# USB2_0_Connector.net
KiCad netlist of a schematic drawn in Altium Designer
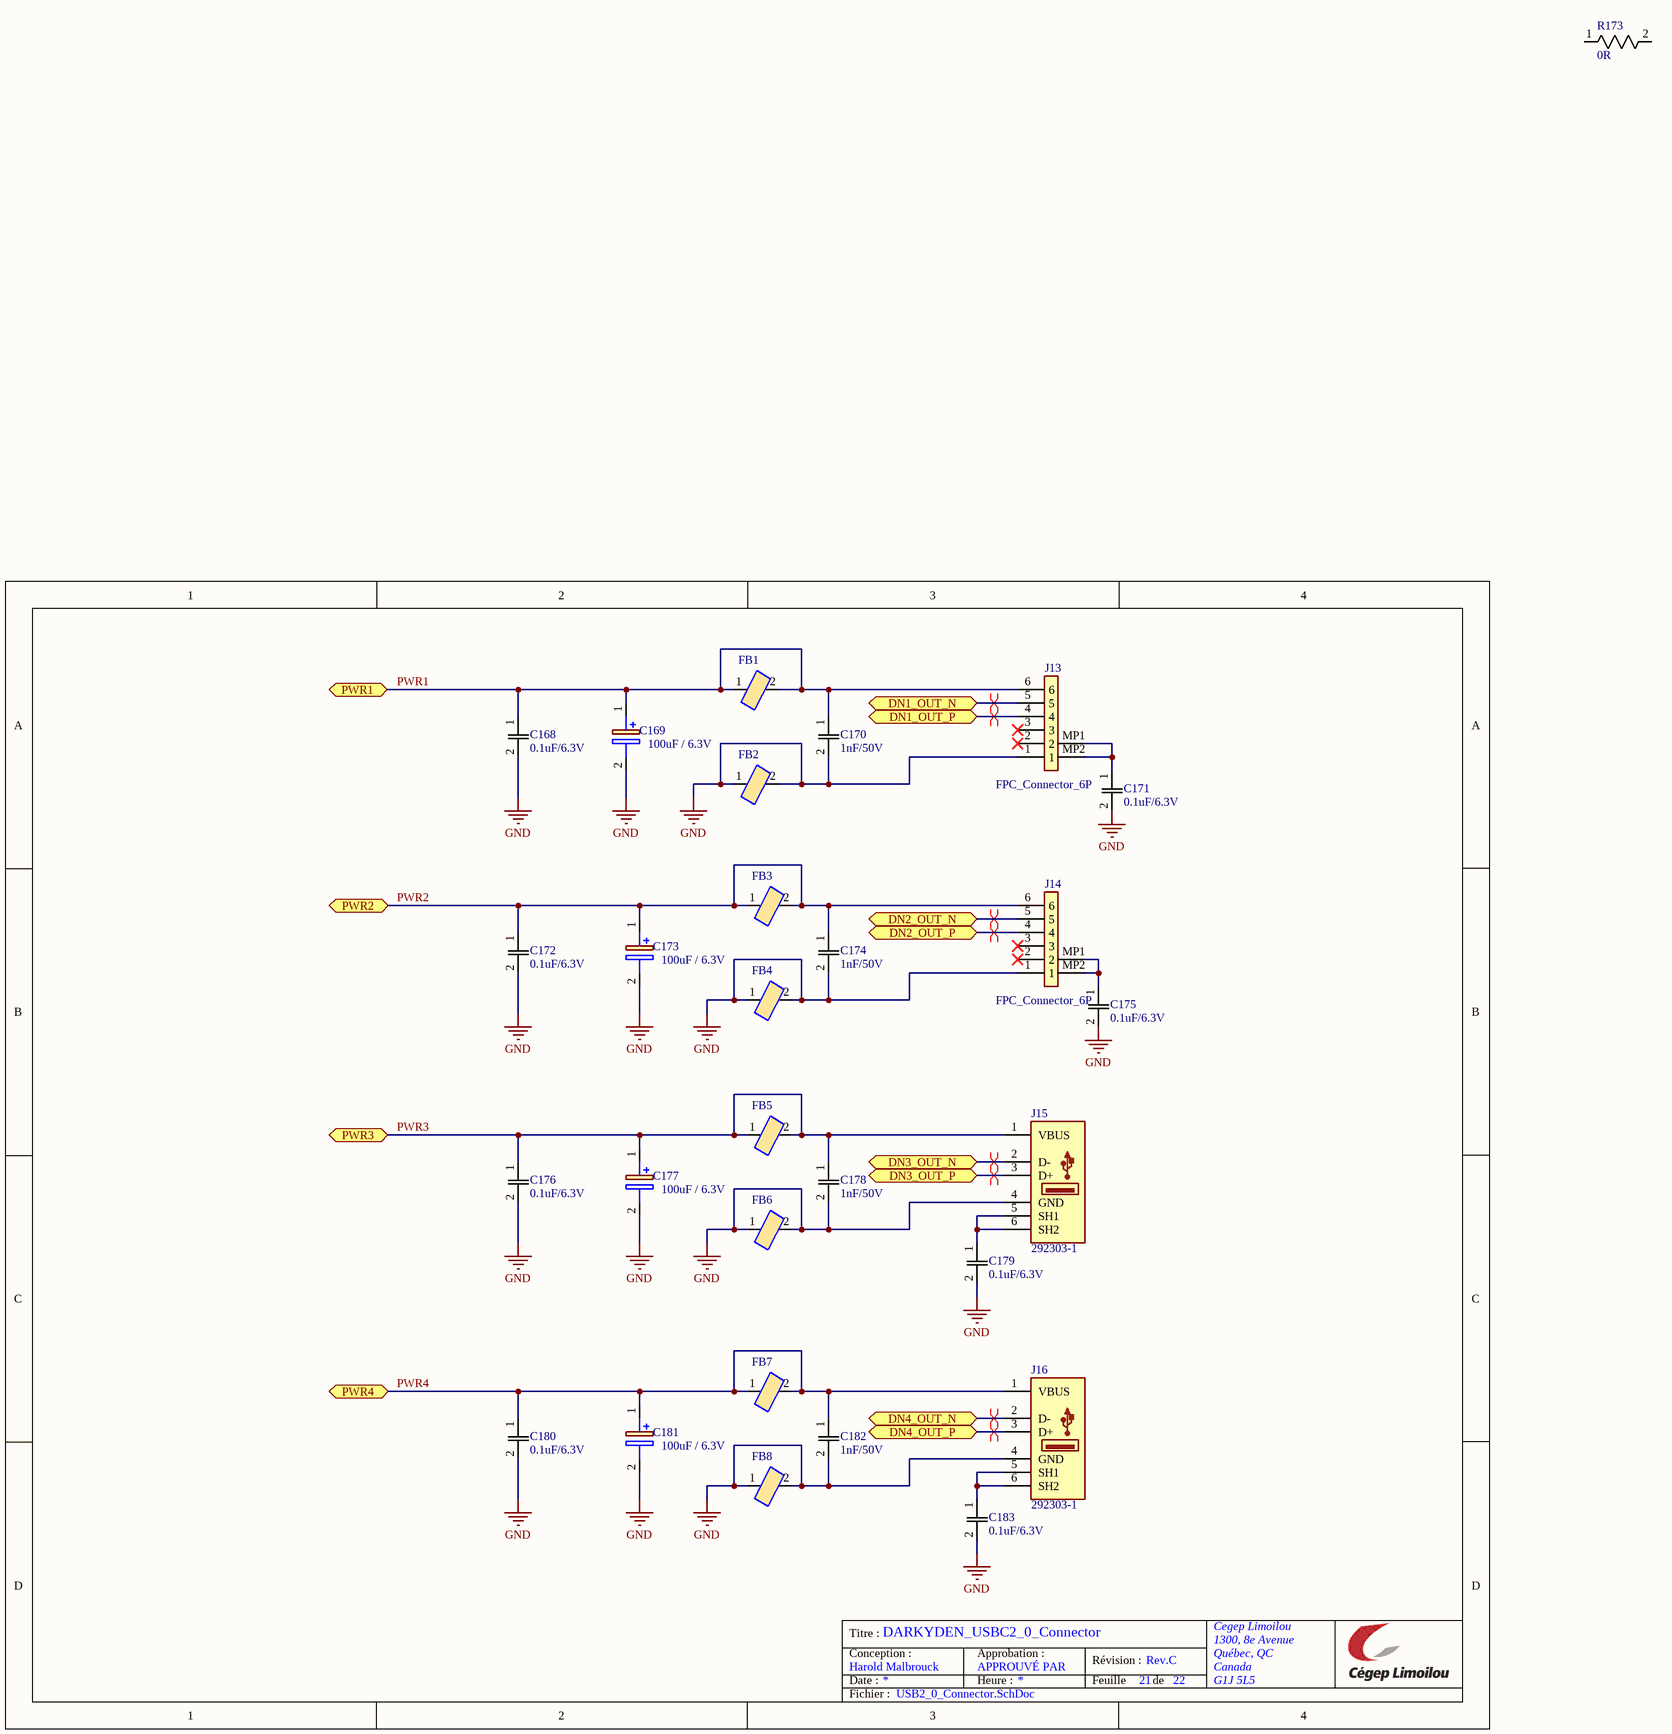
[diagram p0: USB2_0_Connector.SchDoc]

(export (version "E")
  (design (tool "Eeschema 10.0.6"))
  (components
    (comp (ref "C168")
      (value "0.1uF/6.3V")
      (footprint "SamacSys:C0805")
      (description "0.1uF 6.3V X7R 10% Pad SMD 0805 125C T/R")
      (fields
        (field (name "MANUFACTURER_PART_NUMBER") "C0805C104K9RACTU")
        (field (name "MOUSER PART NUMBER") "80-C0805C104K9R")
      )
      (libsource (lib "SamacSys") (part "C0805C104K9RACTU"))
    )
    (comp (ref "C169")
      (value "100uF / 6.3V")
      (footprint "SamacSys:EEE0GA101SR")
      (description "100uF 6.3V 20% Cap Aluminum Lytic  SMD 0.36 Ohm 240mA 2000h 105C Automotive T/R")
      (fields
        (field (name "MANUFACTURER_PART_NUMBER") "EEE-FPJ101UAR")
        (field (name "MOUSER PART NUMBER") "667-EEE-FPJ101UAR")
      )
      (libsource (lib "SamacSys") (part "EEE-FPJ101UAR"))
    )
    (comp (ref "C170")
      (value "1nF/50V")
      (footprint "SamacSys:CAPC2012X88N")
      (description "1000 pF ±10% 50V Ceramic Capacitor X7R 0805 (2012 Metric)")
      (fields (field (name "MANUFACTURER_PART_NUMBER") "C0805C102K5RAC-TU"))
      (libsource (lib "SamacSys") (part "C0805C102K5RAC-TU"))
    )
    (comp (ref "C171")
      (value "0.1uF/6.3V")
      (footprint "SamacSys:C0805")
      (description "0.1uF 6.3V X7R 10% Pad SMD 0805 125C T/R")
      (fields
        (field (name "MANUFACTURER_PART_NUMBER") "C0805C104K9RACTU")
        (field (name "MOUSER PART NUMBER") "80-C0805C104K9R")
      )
      (libsource (lib "SamacSys") (part "C0805C104K9RACTU"))
    )
    (comp (ref "C172")
      (value "0.1uF/6.3V")
      (footprint "SamacSys:C0805")
      (description "0.1uF 6.3V X7R 10% Pad SMD 0805 125C T/R")
      (fields
        (field (name "MANUFACTURER_PART_NUMBER") "C0805C104K9RACTU")
        (field (name "MOUSER PART NUMBER") "80-C0805C104K9R")
      )
      (libsource (lib "SamacSys") (part "C0805C104K9RACTU"))
    )
    (comp (ref "C173")
      (value "100uF / 6.3V")
      (footprint "SamacSys:EEE0GA101SR")
      (description "100uF 6.3V 20% Cap Aluminum Lytic  SMD 0.36 Ohm 240mA 2000h 105C Automotive T/R")
      (fields
        (field (name "MANUFACTURER_PART_NUMBER") "EEE-FPJ101UAR")
        (field (name "MOUSER PART NUMBER") "667-EEE-FPJ101UAR")
      )
      (libsource (lib "SamacSys") (part "EEE-FPJ101UAR"))
    )
    (comp (ref "C174")
      (value "1nF/50V")
      (footprint "SamacSys:CAPC2012X88N")
      (description "1000 pF ±10% 50V Ceramic Capacitor X7R 0805 (2012 Metric)")
      (fields (field (name "MANUFACTURER_PART_NUMBER") "C0805C102K5RAC-TU"))
      (libsource (lib "SamacSys") (part "C0805C102K5RAC-TU"))
    )
    (comp (ref "C175")
      (value "0.1uF/6.3V")
      (footprint "SamacSys:C0805")
      (description "0.1uF 6.3V X7R 10% Pad SMD 0805 125C T/R")
      (fields
        (field (name "MANUFACTURER_PART_NUMBER") "C0805C104K9RACTU")
        (field (name "MOUSER PART NUMBER") "80-C0805C104K9R")
      )
      (libsource (lib "SamacSys") (part "C0805C104K9RACTU"))
    )
    (comp (ref "C176")
      (value "0.1uF/6.3V")
      (footprint "SamacSys:C0805")
      (description "0.1uF 6.3V X7R 10% Pad SMD 0805 125C T/R")
      (fields
        (field (name "MANUFACTURER_PART_NUMBER") "C0805C104K9RACTU")
        (field (name "MOUSER PART NUMBER") "80-C0805C104K9R")
      )
      (libsource (lib "SamacSys") (part "C0805C104K9RACTU"))
    )
    (comp (ref "C177")
      (value "100uF / 6.3V")
      (footprint "SamacSys:EEE0GA101SR")
      (description "100uF 6.3V 20% Cap Aluminum Lytic  SMD 0.36 Ohm 240mA 2000h 105C Automotive T/R")
      (fields
        (field (name "MANUFACTURER_PART_NUMBER") "EEE-FPJ101UAR")
        (field (name "MOUSER PART NUMBER") "667-EEE-FPJ101UAR")
      )
      (libsource (lib "SamacSys") (part "EEE-FPJ101UAR"))
    )
    (comp (ref "C178")
      (value "1nF/50V")
      (footprint "SamacSys:CAPC2012X88N")
      (description "1000 pF ±10% 50V Ceramic Capacitor X7R 0805 (2012 Metric)")
      (fields (field (name "MANUFACTURER_PART_NUMBER") "C0805C102K5RAC-TU"))
      (libsource (lib "SamacSys") (part "C0805C102K5RAC-TU"))
    )
    (comp (ref "C179")
      (value "0.1uF/6.3V")
      (footprint "SamacSys:C0805")
      (description "0.1uF 6.3V X7R 10% Pad SMD 0805 125C T/R")
      (fields
        (field (name "MANUFACTURER_PART_NUMBER") "C0805C104K9RACTU")
        (field (name "MOUSER PART NUMBER") "80-C0805C104K9R")
      )
      (libsource (lib "SamacSys") (part "C0805C104K9RACTU"))
    )
    (comp (ref "C180")
      (value "0.1uF/6.3V")
      (footprint "SamacSys:C0805")
      (description "0.1uF 6.3V X7R 10% Pad SMD 0805 125C T/R")
      (fields
        (field (name "MANUFACTURER_PART_NUMBER") "C0805C104K9RACTU")
        (field (name "MOUSER PART NUMBER") "80-C0805C104K9R")
      )
      (libsource (lib "SamacSys") (part "C0805C104K9RACTU"))
    )
    (comp (ref "C181")
      (value "100uF / 6.3V")
      (footprint "SamacSys:EEE0GA101SR")
      (description "100uF 6.3V 20% Cap Aluminum Lytic  SMD 0.36 Ohm 240mA 2000h 105C Automotive T/R")
      (fields
        (field (name "MANUFACTURER_PART_NUMBER") "EEE-FPJ101UAR")
        (field (name "MOUSER PART NUMBER") "667-EEE-FPJ101UAR")
      )
      (libsource (lib "SamacSys") (part "EEE-FPJ101UAR"))
    )
    (comp (ref "C182")
      (value "1nF/50V")
      (footprint "SamacSys:CAPC2012X88N")
      (description "1000 pF ±10% 50V Ceramic Capacitor X7R 0805 (2012 Metric)")
      (fields (field (name "MANUFACTURER_PART_NUMBER") "C0805C102K5RAC-TU"))
      (libsource (lib "SamacSys") (part "C0805C102K5RAC-TU"))
    )
    (comp (ref "C183")
      (value "0.1uF/6.3V")
      (footprint "SamacSys:C0805")
      (description "0.1uF 6.3V X7R 10% Pad SMD 0805 125C T/R")
      (fields
        (field (name "MANUFACTURER_PART_NUMBER") "C0805C104K9RACTU")
        (field (name "MOUSER PART NUMBER") "80-C0805C104K9R")
      )
      (libsource (lib "SamacSys") (part "C0805C104K9RACTU"))
    )
    (comp (ref "FB1")
      (value "220R / 100MHz")
      (footprint "SamacSys:BLM18SP221SN1B")
      (description "Ferrite Beads Multi-Layer 220Ohm 25% 100MHz 2A 50mOhm DCR 0603 Paper T/R")
      (fields
        (field (name "MANUFACTURER_PART_NUMBER") "BLM18EG221SN1D")
        (field (name "MOUSER PART NUMBER") "81-BLM18EG221SN1D")
      )
      (libsource (lib "SamacSys") (part "BLM18EG221SN1D"))
    )
    (comp (ref "FB2")
      (value "220R / 100MHz")
      (footprint "SamacSys:BLM18SP221SN1B")
      (description "Ferrite Beads Multi-Layer 220Ohm 25% 100MHz 2A 50mOhm DCR 0603 Paper T/R")
      (fields
        (field (name "MANUFACTURER_PART_NUMBER") "BLM18EG221SN1D")
        (field (name "MOUSER PART NUMBER") "81-BLM18EG221SN1D")
      )
      (libsource (lib "SamacSys") (part "BLM18EG221SN1D"))
    )
    (comp (ref "FB3")
      (value "220R / 100MHz")
      (footprint "SamacSys:BLM18SP221SN1B")
      (description "Ferrite Beads Multi-Layer 220Ohm 25% 100MHz 2A 50mOhm DCR 0603 Paper T/R")
      (fields
        (field (name "MANUFACTURER_PART_NUMBER") "BLM18EG221SN1D")
        (field (name "MOUSER PART NUMBER") "81-BLM18EG221SN1D")
      )
      (libsource (lib "SamacSys") (part "BLM18EG221SN1D"))
    )
    (comp (ref "FB4")
      (value "220R / 100MHz")
      (footprint "SamacSys:BLM18SP221SN1B")
      (description "Ferrite Beads Multi-Layer 220Ohm 25% 100MHz 2A 50mOhm DCR 0603 Paper T/R")
      (fields
        (field (name "MANUFACTURER_PART_NUMBER") "BLM18EG221SN1D")
        (field (name "MOUSER PART NUMBER") "81-BLM18EG221SN1D")
      )
      (libsource (lib "SamacSys") (part "BLM18EG221SN1D"))
    )
    (comp (ref "FB5")
      (value "220R / 100MHz")
      (footprint "SamacSys:BLM18SP221SN1B")
      (description "Ferrite Beads Multi-Layer 220Ohm 25% 100MHz 2A 50mOhm DCR 0603 Paper T/R")
      (fields
        (field (name "MANUFACTURER_PART_NUMBER") "BLM18EG221SN1D")
        (field (name "MOUSER PART NUMBER") "81-BLM18EG221SN1D")
      )
      (libsource (lib "SamacSys") (part "BLM18EG221SN1D"))
    )
    (comp (ref "FB6")
      (value "220R / 100MHz")
      (footprint "SamacSys:BLM18SP221SN1B")
      (description "Ferrite Beads Multi-Layer 220Ohm 25% 100MHz 2A 50mOhm DCR 0603 Paper T/R")
      (fields
        (field (name "MANUFACTURER_PART_NUMBER") "BLM18EG221SN1D")
        (field (name "MOUSER PART NUMBER") "81-BLM18EG221SN1D")
      )
      (libsource (lib "SamacSys") (part "BLM18EG221SN1D"))
    )
    (comp (ref "FB7")
      (value "220R / 100MHz")
      (footprint "SamacSys:BLM18SP221SN1B")
      (description "Ferrite Beads Multi-Layer 220Ohm 25% 100MHz 2A 50mOhm DCR 0603 Paper T/R")
      (fields
        (field (name "MANUFACTURER_PART_NUMBER") "BLM18EG221SN1D")
        (field (name "MOUSER PART NUMBER") "81-BLM18EG221SN1D")
      )
      (libsource (lib "SamacSys") (part "BLM18EG221SN1D"))
    )
    (comp (ref "FB8")
      (value "220R / 100MHz")
      (footprint "SamacSys:BLM18SP221SN1B")
      (description "Ferrite Beads Multi-Layer 220Ohm 25% 100MHz 2A 50mOhm DCR 0603 Paper T/R")
      (fields
        (field (name "MANUFACTURER_PART_NUMBER") "BLM18EG221SN1D")
        (field (name "MOUSER PART NUMBER") "81-BLM18EG221SN1D")
      )
      (libsource (lib "SamacSys") (part "BLM18EG221SN1D"))
    )
    (comp (ref "J13")
      (value "FPC_Connector_6P")
      (footprint "SamacSys:23287026")
      (description "FPC Connector; 0.5mm pitch dual contact back flip FPC, 6pos ¦ TE Connectivity 2328702-6")
      (fields
        (field (name "MANUFACTURER_PART_NUMBER") "2328702-6")
        (field (name "MOUSER PART NUMBER") "571-2328702-6")
      )
      (libsource (lib "SamacSys") (part "2328702-6"))
    )
    (comp (ref "J14")
      (value "FPC_Connector_6P")
      (footprint "SamacSys:23287026")
      (description "FPC Connector; 0.5mm pitch dual contact back flip FPC, 6pos ¦ TE Connectivity 2328702-6")
      (fields
        (field (name "MANUFACTURER_PART_NUMBER") "2328702-6")
        (field (name "MOUSER PART NUMBER") "571-2328702-6")
      )
      (libsource (lib "SamacSys") (part "2328702-6"))
    )
    (comp (ref "J15")
      (value "292303-1")
      (footprint "SamacSys:TECONN-4POS-USB")
      (description "USB-A (USB TYPE-A) USB 2.0 Receptacle Connector 4 Position Through Hole, Right Angle")
      (fields (field (name "MOUSER PART NUMBER") "571-292303-1"))
      (libsource (lib "SamacSys") (part "292303-1"))
    )
    (comp (ref "J16")
      (value "292303-1")
      (footprint "SamacSys:TECONN-4POS-USB")
      (description "USB-A (USB TYPE-A) USB 2.0 Receptacle Connector 4 Position Through Hole, Right Angle")
      (fields (field (name "MOUSER PART NUMBER") "571-292303-1"))
      (libsource (lib "SamacSys") (part "292303-1"))
    )
    (comp (ref "R173")
      (value "0R")
      (footprint "SamacSys:ERJ3EKF1000V")
      (description "Zero Ohm Resistor, Jumper, 0603 [1608 Metric], Thick Film, 100 mW, 1 A, Surface Mount")
      (fields
        (field (name "MANUFACTURER_PART_NUMBER") "ERJ-3GEY0R00V")
        (field (name "MOUSER PART NUMBER") "667-ERJ-3GEY0R00V")
      )
      (libsource (lib "SamacSys") (part "ERJ-3GEY0R00V"))
    )
  )
  (nets
    (net (code "1") (name "/DN1_OUT_N") (class "Default")
      (node (ref "J13") (pin "5") (pinfunction "5_5") (pintype "passive"))
    )
    (net (code "2") (name "/DN1_OUT_P") (class "Default")
      (node (ref "J13") (pin "4") (pinfunction "4_4") (pintype "passive"))
    )
    (net (code "3") (name "/DN2_OUT_N") (class "Default")
      (node (ref "J14") (pin "5") (pinfunction "5_5") (pintype "passive"))
    )
    (net (code "4") (name "/DN2_OUT_P") (class "Default")
      (node (ref "J14") (pin "4") (pinfunction "4_4") (pintype "passive"))
    )
    (net (code "5") (name "/DN3_OUT_N") (class "Default")
      (node (ref "J15") (pin "2") (pinfunction "D-_2") (pintype "passive"))
    )
    (net (code "6") (name "/DN3_OUT_P") (class "Default")
      (node (ref "J15") (pin "3") (pinfunction "D+_3") (pintype "passive"))
    )
    (net (code "7") (name "/DN4_OUT_N") (class "Default")
      (node (ref "J16") (pin "2") (pinfunction "D-_2") (pintype "passive"))
    )
    (net (code "8") (name "/DN4_OUT_P") (class "Default")
      (node (ref "J16") (pin "3") (pinfunction "D+_3") (pintype "passive"))
    )
    (net (code "9") (name "/PWR1") (class "Default")
      (node (ref "C168") (pin "1") (pinfunction "1_1") (pintype "passive"))
      (node (ref "C169") (pin "1") (pinfunction "+_1") (pintype "passive"))
      (node (ref "C170") (pin "1") (pinfunction "1_1") (pintype "passive"))
      (node (ref "FB1") (pin "1") (pinfunction "1_1") (pintype "passive"))
      (node (ref "FB1") (pin "2") (pinfunction "2_2") (pintype "passive"))
      (node (ref "J13") (pin "6") (pinfunction "6_6") (pintype "passive"))
    )
    (net (code "10") (name "/PWR2") (class "Default")
      (node (ref "C172") (pin "1") (pinfunction "1_1") (pintype "passive"))
      (node (ref "C173") (pin "1") (pinfunction "+_1") (pintype "passive"))
      (node (ref "C174") (pin "1") (pinfunction "1_1") (pintype "passive"))
      (node (ref "FB3") (pin "1") (pinfunction "1_1") (pintype "passive"))
      (node (ref "FB3") (pin "2") (pinfunction "2_2") (pintype "passive"))
      (node (ref "J14") (pin "6") (pinfunction "6_6") (pintype "passive"))
    )
    (net (code "11") (name "/PWR3") (class "Default")
      (node (ref "C176") (pin "1") (pinfunction "1_1") (pintype "passive"))
      (node (ref "C177") (pin "1") (pinfunction "+_1") (pintype "passive"))
      (node (ref "C178") (pin "1") (pinfunction "1_1") (pintype "passive"))
      (node (ref "FB5") (pin "1") (pinfunction "1_1") (pintype "passive"))
      (node (ref "FB5") (pin "2") (pinfunction "2_2") (pintype "passive"))
      (node (ref "J15") (pin "1") (pinfunction "VBUS_1") (pintype "passive"))
    )
    (net (code "12") (name "/PWR4") (class "Default")
      (node (ref "C180") (pin "1") (pinfunction "1_1") (pintype "passive"))
      (node (ref "C181") (pin "1") (pinfunction "+_1") (pintype "passive"))
      (node (ref "C182") (pin "1") (pinfunction "1_1") (pintype "passive"))
      (node (ref "FB7") (pin "1") (pinfunction "1_1") (pintype "passive"))
      (node (ref "FB7") (pin "2") (pinfunction "2_2") (pintype "passive"))
      (node (ref "J16") (pin "1") (pinfunction "VBUS_1") (pintype "passive"))
    )
    (net (code "13") (name "GND") (class "Default")
      (node (ref "C168") (pin "2") (pinfunction "2_2") (pintype "passive"))
      (node (ref "C169") (pin "2") (pinfunction "-_2") (pintype "passive"))
      (node (ref "C170") (pin "2") (pinfunction "2_2") (pintype "passive"))
      (node (ref "C171") (pin "2") (pinfunction "2_2") (pintype "passive"))
      (node (ref "C172") (pin "2") (pinfunction "2_2") (pintype "passive"))
      (node (ref "C173") (pin "2") (pinfunction "-_2") (pintype "passive"))
      (node (ref "C174") (pin "2") (pinfunction "2_2") (pintype "passive"))
      (node (ref "C175") (pin "2") (pinfunction "2_2") (pintype "passive"))
      (node (ref "C176") (pin "2") (pinfunction "2_2") (pintype "passive"))
      (node (ref "C177") (pin "2") (pinfunction "-_2") (pintype "passive"))
      (node (ref "C178") (pin "2") (pinfunction "2_2") (pintype "passive"))
      (node (ref "C179") (pin "2") (pinfunction "2_2") (pintype "passive"))
      (node (ref "C180") (pin "2") (pinfunction "2_2") (pintype "passive"))
      (node (ref "C181") (pin "2") (pinfunction "-_2") (pintype "passive"))
      (node (ref "C182") (pin "2") (pinfunction "2_2") (pintype "passive"))
      (node (ref "C183") (pin "2") (pinfunction "2_2") (pintype "passive"))
      (node (ref "FB2") (pin "1") (pinfunction "1_1") (pintype "passive"))
      (node (ref "FB2") (pin "2") (pinfunction "2_2") (pintype "passive"))
      (node (ref "FB4") (pin "1") (pinfunction "1_1") (pintype "passive"))
      (node (ref "FB4") (pin "2") (pinfunction "2_2") (pintype "passive"))
      (node (ref "FB6") (pin "1") (pinfunction "1_1") (pintype "passive"))
      (node (ref "FB6") (pin "2") (pinfunction "2_2") (pintype "passive"))
      (node (ref "FB8") (pin "1") (pinfunction "1_1") (pintype "passive"))
      (node (ref "FB8") (pin "2") (pinfunction "2_2") (pintype "passive"))
      (node (ref "J13") (pin "1") (pinfunction "1_1") (pintype "passive"))
      (node (ref "J14") (pin "1") (pinfunction "1_1") (pintype "passive"))
      (node (ref "J15") (pin "4") (pinfunction "GND_4") (pintype "passive"))
      (node (ref "J16") (pin "4") (pinfunction "GND_4") (pintype "passive"))
    )
    (net (code "14") (name "Net-(C171-Pad1)") (class "Default")
      (node (ref "C171") (pin "1") (pinfunction "1_1") (pintype "passive"))
      (node (ref "J13") (pin "MP1") (pinfunction "MP1_MP1") (pintype "passive"))
      (node (ref "J13") (pin "MP2") (pinfunction "MP2_MP2") (pintype "passive"))
    )
    (net (code "15") (name "Net-(C175-Pad1)") (class "Default")
      (node (ref "C175") (pin "1") (pinfunction "1_1") (pintype "passive"))
      (node (ref "J14") (pin "MP1") (pinfunction "MP1_MP1") (pintype "passive"))
      (node (ref "J14") (pin "MP2") (pinfunction "MP2_MP2") (pintype "passive"))
    )
    (net (code "16") (name "Net-(J15-SH1)") (class "Default")
      (node (ref "C179") (pin "1") (pinfunction "1_1") (pintype "passive"))
      (node (ref "J15") (pin "5") (pinfunction "SH1_5") (pintype "passive"))
      (node (ref "J15") (pin "6") (pinfunction "SH2_6") (pintype "passive"))
    )
    (net (code "17") (name "Net-(J16-SH1)") (class "Default")
      (node (ref "C183") (pin "1") (pinfunction "1_1") (pintype "passive"))
      (node (ref "J16") (pin "5") (pinfunction "SH1_5") (pintype "passive"))
      (node (ref "J16") (pin "6") (pinfunction "SH2_6") (pintype "passive"))
    )
    (net (code "18") (name "unconnected-(J13-Pad2)") (class "Default")
      (node (ref "J13") (pin "2") (pinfunction "2_2") (pintype "passive+no_connect"))
    )
    (net (code "19") (name "unconnected-(J13-Pad3)") (class "Default")
      (node (ref "J13") (pin "3") (pinfunction "3_3") (pintype "passive+no_connect"))
    )
    (net (code "20") (name "unconnected-(J14-Pad2)") (class "Default")
      (node (ref "J14") (pin "2") (pinfunction "2_2") (pintype "passive+no_connect"))
    )
    (net (code "21") (name "unconnected-(J14-Pad3)") (class "Default")
      (node (ref "J14") (pin "3") (pinfunction "3_3") (pintype "passive+no_connect"))
    )
    (net (code "22") (name "unconnected-(R173-Pad1)") (class "Default")
      (node (ref "R173") (pin "1") (pinfunction "1_1") (pintype "passive"))
    )
    (net (code "23") (name "unconnected-(R173-Pad2)") (class "Default")
      (node (ref "R173") (pin "2") (pinfunction "2_2") (pintype "passive"))
    )
  )
)
